# RePhone_core_2G-Atmel32u4_v1_0.net
KiCad netlist of a schematic drawn in EAGLE
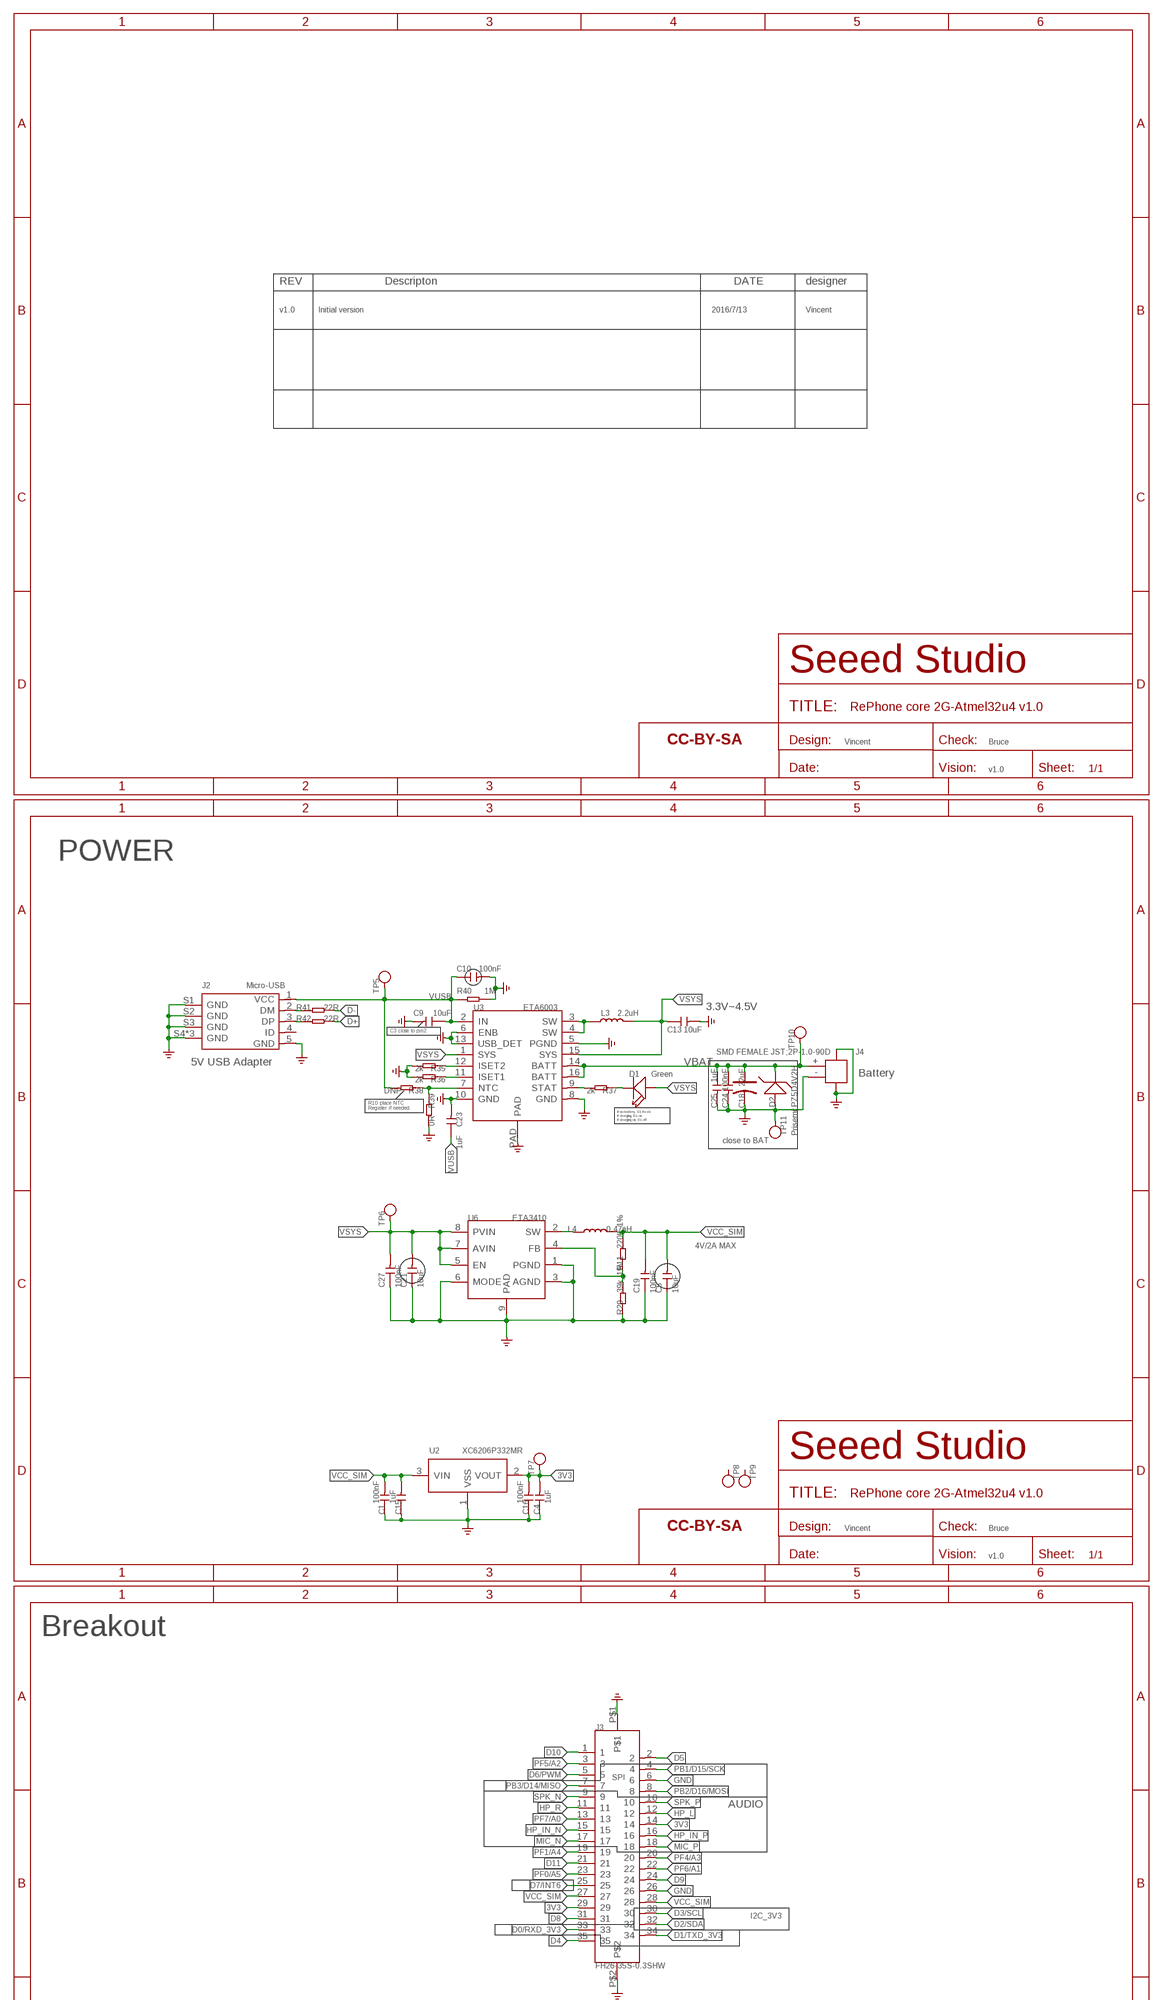
[diagram p0: schematic, sheet 1, part 1 of 2]
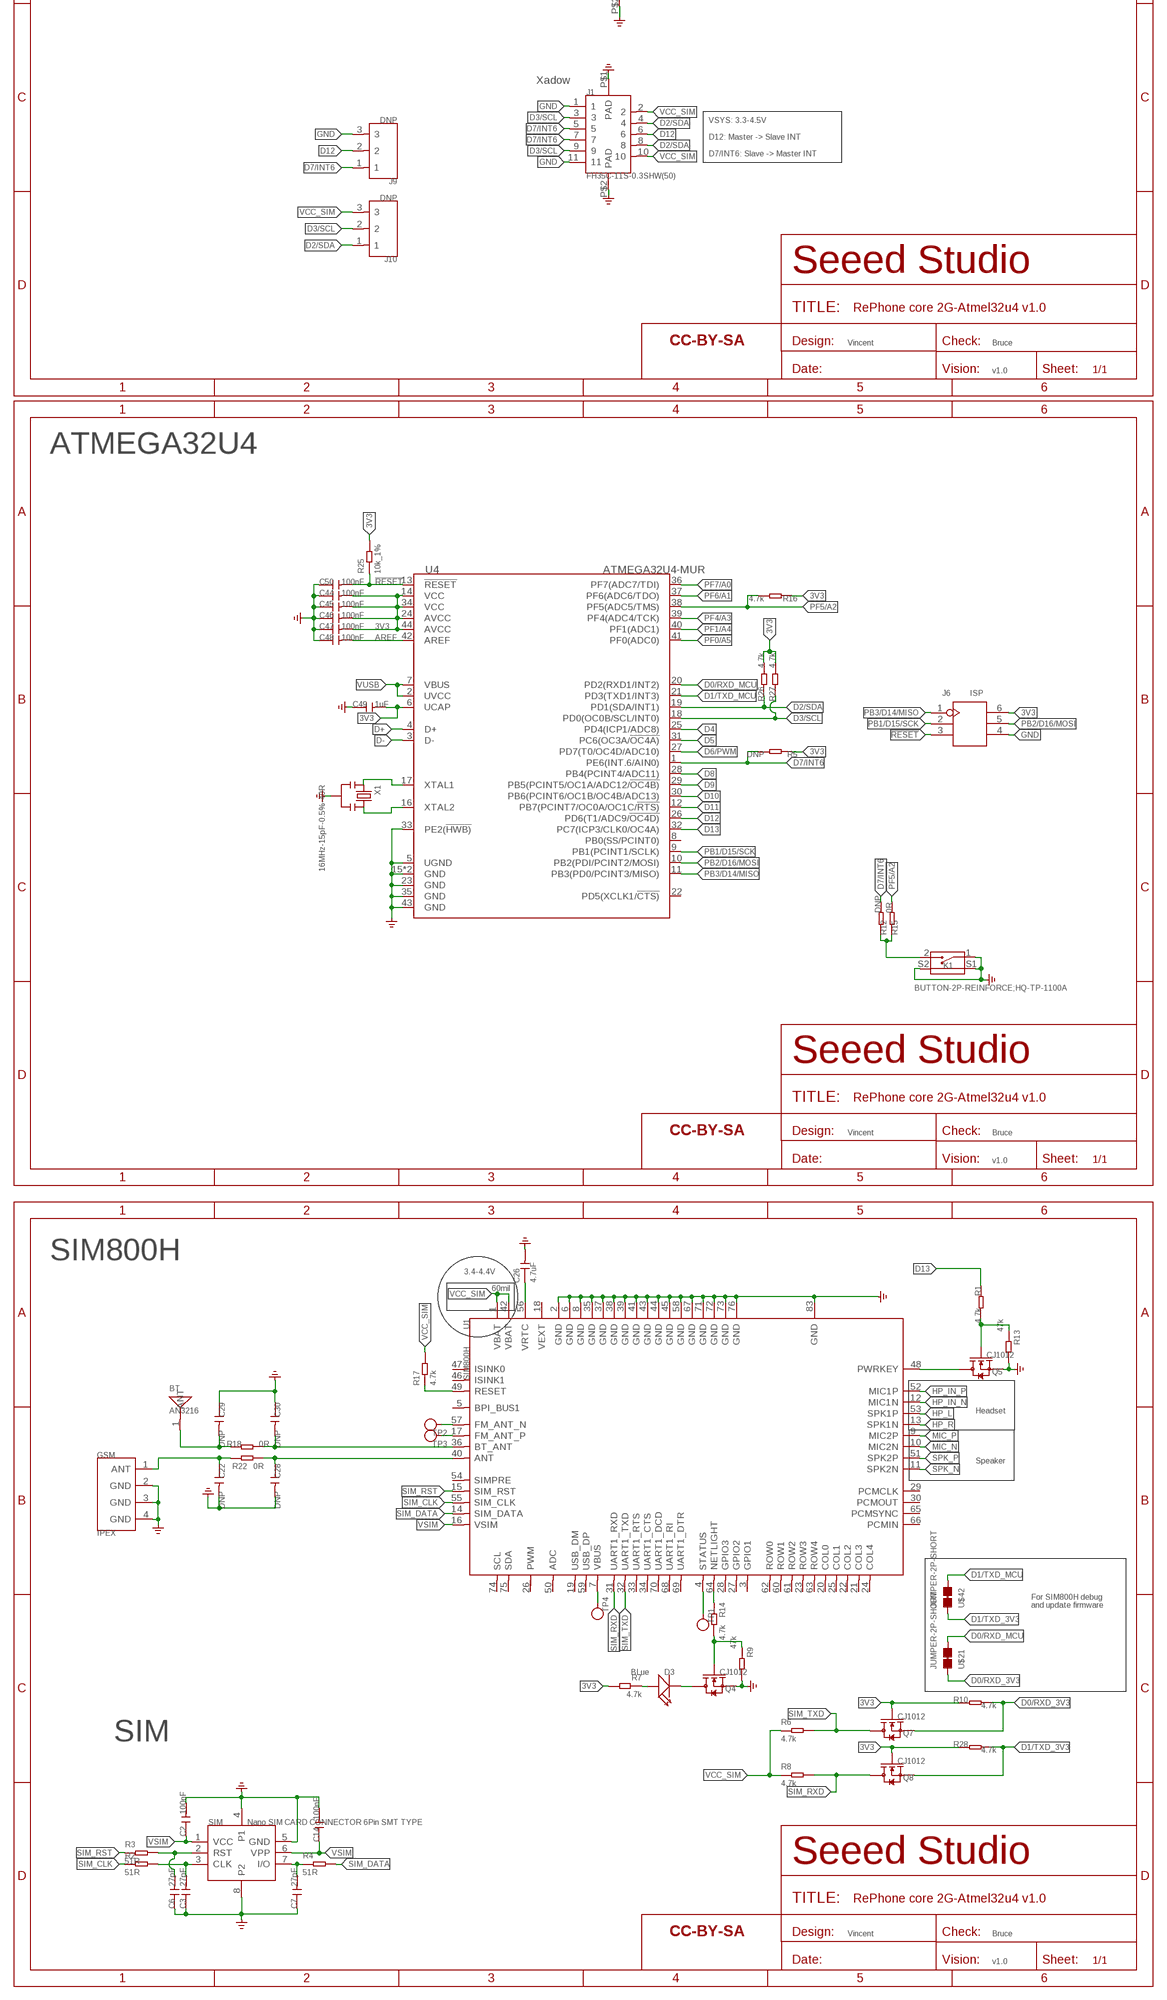
[diagram p1: schematic, sheet 1, part 2 of 2]

(export (version "E")
  (design (tool "Eeschema 10.0.6"))
  (components
    (comp (ref "BT")
      (value "AN3216")
      (footprint "eagle-import:ANT-SMD2P-3.2X1.6X1.04MM")
      (libsource (lib "eagle-import") (part "ANTENNA-AN3216"))
    )
    (comp (ref "C1")
      (value "100nF")
      (footprint "eagle-import:C0201")
      (libsource (lib "eagle-import") (part "CAP-0201"))
    )
    (comp (ref "C2")
      (value "100nF")
      (footprint "eagle-import:C0201")
      (libsource (lib "eagle-import") (part "CAP-0201"))
    )
    (comp (ref "C3")
      (value "27pF")
      (footprint "eagle-import:C0201")
      (libsource (lib "eagle-import") (part "CAP-0201"))
    )
    (comp (ref "C4")
      (value "1uF")
      (footprint "eagle-import:C0402")
      (libsource (lib "eagle-import") (part "CAP-0402"))
    )
    (comp (ref "C5")
      (value "10uF")
      (footprint "eagle-import:C0603")
      (libsource (lib "eagle-import") (part "CAP-0603"))
    )
    (comp (ref "C6")
      (value "27pF")
      (footprint "eagle-import:C0201")
      (libsource (lib "eagle-import") (part "CAP-0201"))
    )
    (comp (ref "C7")
      (value "27pF")
      (footprint "eagle-import:C0201")
      (libsource (lib "eagle-import") (part "CAP-0201"))
    )
    (comp (ref "C9")
      (value "10uF")
      (footprint "eagle-import:C0603")
      (libsource (lib "eagle-import") (part "CAP-0603"))
    )
    (comp (ref "C10")
      (value "100nF")
      (footprint "eagle-import:C0201")
      (libsource (lib "eagle-import") (part "CAP-0201"))
    )
    (comp (ref "C13")
      (value "10uF")
      (footprint "eagle-import:C0603")
      (libsource (lib "eagle-import") (part "CAP-0603"))
    )
    (comp (ref "C14")
      (value "100nF")
      (footprint "eagle-import:C0201")
      (libsource (lib "eagle-import") (part "CAP-0201"))
    )
    (comp (ref "C15")
      (value "1uF")
      (footprint "eagle-import:C0402")
      (libsource (lib "eagle-import") (part "CAP-0402"))
    )
    (comp (ref "C16")
      (value "100nF")
      (footprint "eagle-import:C0201")
      (libsource (lib "eagle-import") (part "CAP-0201"))
    )
    (comp (ref "C18")
      (value "22uF")
      (footprint "eagle-import:AVX-A")
      (libsource (lib "eagle-import") (part "CAP-POLAR-AVX-A"))
    )
    (comp (ref "C19")
      (value "100nF")
      (footprint "eagle-import:C0201")
      (libsource (lib "eagle-import") (part "CAP-0201"))
    )
    (comp (ref "C21")
      (value "10uF")
      (footprint "eagle-import:C0603")
      (libsource (lib "eagle-import") (part "CAP-0603"))
    )
    (comp (ref "C22")
      (value "DNP")
      (footprint "eagle-import:C0201")
      (libsource (lib "eagle-import") (part "CAP-0201"))
    )
    (comp (ref "C23")
      (value "1uF")
      (footprint "eagle-import:C0402")
      (libsource (lib "eagle-import") (part "CAP-0402"))
    )
    (comp (ref "C24")
      (value "100nF")
      (footprint "eagle-import:C0201")
      (libsource (lib "eagle-import") (part "CAP-0201"))
    )
    (comp (ref "C25")
      (value "1uF")
      (footprint "eagle-import:C0402")
      (libsource (lib "eagle-import") (part "CAP-0402"))
    )
    (comp (ref "C26")
      (value "4.7uF")
      (footprint "eagle-import:C0603")
      (libsource (lib "eagle-import") (part "CAP-0603"))
    )
    (comp (ref "C27")
      (value "100nF")
      (footprint "eagle-import:C0201")
      (libsource (lib "eagle-import") (part "CAP-0201"))
    )
    (comp (ref "C28")
      (value "DNP")
      (footprint "eagle-import:C0201")
      (libsource (lib "eagle-import") (part "CAP-0201"))
    )
    (comp (ref "C29")
      (value "DNP")
      (footprint "eagle-import:C0201")
      (libsource (lib "eagle-import") (part "CAP-0201"))
    )
    (comp (ref "C30")
      (value "DNP")
      (footprint "eagle-import:C0201")
      (libsource (lib "eagle-import") (part "CAP-0201"))
    )
    (comp (ref "C44")
      (value "100nF")
      (footprint "eagle-import:C0201")
      (libsource (lib "eagle-import") (part "CAP-0201"))
    )
    (comp (ref "C45")
      (value "100nF")
      (footprint "eagle-import:C0201")
      (libsource (lib "eagle-import") (part "CAP-0201"))
    )
    (comp (ref "C46")
      (value "100nF")
      (footprint "eagle-import:C0201")
      (libsource (lib "eagle-import") (part "CAP-0201"))
    )
    (comp (ref "C47")
      (value "100nF")
      (footprint "eagle-import:C0201")
      (libsource (lib "eagle-import") (part "CAP-0201"))
    )
    (comp (ref "C48")
      (value "100nF")
      (footprint "eagle-import:C0201")
      (libsource (lib "eagle-import") (part "CAP-0201"))
    )
    (comp (ref "C49")
      (value "1uF")
      (footprint "eagle-import:C0402")
      (libsource (lib "eagle-import") (part "CAP-0402"))
    )
    (comp (ref "C50")
      (value "100nF")
      (footprint "eagle-import:C0201")
      (libsource (lib "eagle-import") (part "CAP-0201"))
    )
    (comp (ref "D1")
      (value "Green")
      (footprint "eagle-import:LED-0402")
      (libsource (lib "eagle-import") (part "LED-0402"))
    )
    (comp (ref "D2")
      (value "Prisemi;PZ5D4V2H")
      (footprint "eagle-import:SOD-523")
      (libsource (lib "eagle-import") (part "D-ZENER-2P'BZX584CX'"))
    )
    (comp (ref "D3")
      (value "BLue")
      (footprint "eagle-import:LED-0402")
      (libsource (lib "eagle-import") (part "LED-0402"))
    )
    (comp (ref "FR1")
      (value "SEEEDSTUDIO-OPEN-SCH-FRAME")
      (footprint "eagle-import:SEEEDSTUDIO-PCB-FRAME")
      (libsource (lib "eagle-import") (part "SEEEDSTUDIO-OPEN-SCH-FRAME"))
    )
    (comp (ref "FR2")
      (value "SEEEDSTUDIO-OPEN-SCH-FRAME")
      (footprint "eagle-import:SEEEDSTUDIO-PCB-FRAME")
      (libsource (lib "eagle-import") (part "SEEEDSTUDIO-OPEN-SCH-FRAME"))
    )
    (comp (ref "GSM")
      (value "IPEX")
      (footprint "eagle-import:ANT-IPEX4-1.7X1.7MM")
      (libsource (lib "eagle-import") (part "ANT_IPEX"))
    )
    (comp (ref "J1")
      (value "FH35C-11S-0.3SHW(50)")
      (footprint "eagle-import:FPC11-SMD-0.3(FH35C)")
      (libsource (lib "eagle-import") (part "FPC-CONNECTER-11P(FH35C-11S-0.3SHW(50))"))
    )
    (comp (ref "J2")
      (value "Micro-USB")
      (footprint "eagle-import:MICRO-USB5+4P-SMD-0.65-B")
      (libsource (lib "eagle-import") (part "MICRO-USB5+4P5+4P"))
    )
    (comp (ref "J3")
      (value "FH26-35S-0.3SHW")
      (footprint "eagle-import:FPC35-SMD-0.3(FH26W)")
      (libsource (lib "eagle-import") (part "FPC-CONNECTER-35P(FH26W-35S-0.3SHW(10))"))
    )
    (comp (ref "J4")
      (value "SMD FEMALE JST;2P-1.0-90D")
      (footprint "eagle-import:HW2-SMD-1.0-90D")
      (libsource (lib "eagle-import") (part "JST-2P-SMD'1.0'"))
    )
    (comp (ref "J6")
      (value "ISP")
      (footprint "eagle-import:H2X3-SMD-2.0(1.143)")
      (libsource (lib "eagle-import") (part "HEADER-2X3P-2.0-1.143"))
    )
    (comp (ref "J9")
      (value "DNP")
      (footprint "eagle-import:3P-DIP-2")
      (libsource (lib "eagle-import") (part "HEADER3"))
    )
    (comp (ref "J10")
      (value "DNP")
      (footprint "eagle-import:3P-DIP-2")
      (libsource (lib "eagle-import") (part "HEADER3"))
    )
    (comp (ref "K1")
      (value "BUTTON-2P-REINFORCE;HQ-TP-1100A")
      (footprint "eagle-import:SW4-SMD-4.5X3.8X1.8MM-90D")
      (libsource (lib "eagle-import") (part "BUTTON-2+2P'HQ-TP-1100A'"))
    )
    (comp (ref "L3")
      (value "2.2uH")
      (footprint "eagle-import:L0805")
      (libsource (lib "eagle-import") (part "INDUCTOR/FERRITE-BEAD'0805'"))
    )
    (comp (ref "L4")
      (value "0.47uH")
      (footprint "eagle-import:L201610")
      (libsource (lib "eagle-import") (part "L-MPM201610SR33_T"))
    )
    (comp (ref "Q4")
      (value "CJ1012")
      (footprint "eagle-import:SOT-523")
      (libsource (lib "eagle-import") (part "MOSFET-N"))
    )
    (comp (ref "Q5")
      (value "CJ1012")
      (footprint "eagle-import:SOT-523")
      (libsource (lib "eagle-import") (part "MOSFET-N"))
    )
    (comp (ref "Q7")
      (value "CJ1012")
      (footprint "eagle-import:SOT-523")
      (libsource (lib "eagle-import") (part "MOSFET-N"))
    )
    (comp (ref "Q8")
      (value "CJ1012")
      (footprint "eagle-import:SOT-523")
      (libsource (lib "eagle-import") (part "MOSFET-N"))
    )
    (comp (ref "R1")
      (value "4.7k")
      (footprint "eagle-import:R0201")
      (libsource (lib "eagle-import") (part "RES-0201"))
    )
    (comp (ref "R2")
      (value "51R")
      (footprint "eagle-import:R0201")
      (libsource (lib "eagle-import") (part "RES-0201"))
    )
    (comp (ref "R3")
      (value "51R")
      (footprint "eagle-import:R0201")
      (libsource (lib "eagle-import") (part "RES-0201"))
    )
    (comp (ref "R4")
      (value "51R")
      (footprint "eagle-import:R0201")
      (libsource (lib "eagle-import") (part "RES-0201"))
    )
    (comp (ref "R5")
      (value "DNP")
      (footprint "eagle-import:R0201")
      (libsource (lib "eagle-import") (part "RES-0201"))
    )
    (comp (ref "R6")
      (value "4.7k")
      (footprint "eagle-import:R0201")
      (libsource (lib "eagle-import") (part "RES-0201"))
    )
    (comp (ref "R7")
      (value "4.7k")
      (footprint "eagle-import:R0201")
      (libsource (lib "eagle-import") (part "RES-0201"))
    )
    (comp (ref "R8")
      (value "4.7k")
      (footprint "eagle-import:R0201")
      (libsource (lib "eagle-import") (part "RES-0201"))
    )
    (comp (ref "R9")
      (value "47k")
      (footprint "eagle-import:R0201")
      (libsource (lib "eagle-import") (part "RES-0201"))
    )
    (comp (ref "R10")
      (value "4.7k")
      (footprint "eagle-import:R0201")
      (libsource (lib "eagle-import") (part "RES-0201"))
    )
    (comp (ref "R11")
      (value "220k_1%")
      (footprint "eagle-import:R0201")
      (libsource (lib "eagle-import") (part "RES-0201"))
    )
    (comp (ref "R12")
      (value "DNP")
      (footprint "eagle-import:R0201")
      (libsource (lib "eagle-import") (part "RES-0201"))
    )
    (comp (ref "R13")
      (value "47k")
      (footprint "eagle-import:R0201")
      (libsource (lib "eagle-import") (part "RES-0201"))
    )
    (comp (ref "R14")
      (value "4.7k")
      (footprint "eagle-import:R0201")
      (libsource (lib "eagle-import") (part "RES-0201"))
    )
    (comp (ref "R15")
      (value "0R")
      (footprint "eagle-import:R0201")
      (libsource (lib "eagle-import") (part "RES-0201"))
    )
    (comp (ref "R16")
      (value "4.7k")
      (footprint "eagle-import:R0201")
      (libsource (lib "eagle-import") (part "RES-0201"))
    )
    (comp (ref "R17")
      (value "4.7k")
      (footprint "eagle-import:R0201")
      (libsource (lib "eagle-import") (part "RES-0201"))
    )
    (comp (ref "R18")
      (value "0R")
      (footprint "eagle-import:R0201")
      (libsource (lib "eagle-import") (part "RES-0201"))
    )
    (comp (ref "R22")
      (value "0R")
      (footprint "eagle-import:R0201")
      (libsource (lib "eagle-import") (part "RES-0201"))
    )
    (comp (ref "R25")
      (value "10k_1%")
      (footprint "eagle-import:R0201")
      (libsource (lib "eagle-import") (part "RES-0201"))
    )
    (comp (ref "R26")
      (value "4.7k")
      (footprint "eagle-import:R0201")
      (libsource (lib "eagle-import") (part "RES-0201"))
    )
    (comp (ref "R27")
      (value "4.7k")
      (footprint "eagle-import:R0201")
      (libsource (lib "eagle-import") (part "RES-0201"))
    )
    (comp (ref "R28")
      (value "4.7k")
      (footprint "eagle-import:R0201")
      (libsource (lib "eagle-import") (part "RES-0201"))
    )
    (comp (ref "R29")
      (value "39k_1%")
      (footprint "eagle-import:R0201")
      (libsource (lib "eagle-import") (part "RES-0201"))
    )
    (comp (ref "R35")
      (value "2k")
      (footprint "eagle-import:R0201")
      (libsource (lib "eagle-import") (part "RES-0201"))
    )
    (comp (ref "R36")
      (value "2k")
      (footprint "eagle-import:R0201")
      (libsource (lib "eagle-import") (part "RES-0201"))
    )
    (comp (ref "R37")
      (value "2k")
      (footprint "eagle-import:R0201")
      (libsource (lib "eagle-import") (part "RES-0201"))
    )
    (comp (ref "R38")
      (value "DNP")
      (footprint "eagle-import:R0201")
      (libsource (lib "eagle-import") (part "RES-0201"))
    )
    (comp (ref "R39")
      (value "0R")
      (footprint "eagle-import:R0201")
      (libsource (lib "eagle-import") (part "RES-0201"))
    )
    (comp (ref "R40")
      (value "1M")
      (footprint "eagle-import:R0201")
      (libsource (lib "eagle-import") (part "RES-0201"))
    )
    (comp (ref "R41")
      (value "22R")
      (footprint "eagle-import:R0201")
      (libsource (lib "eagle-import") (part "RES-0201"))
    )
    (comp (ref "R42")
      (value "22R")
      (footprint "eagle-import:R0201")
      (libsource (lib "eagle-import") (part "RES-0201"))
    )
    (comp (ref "SIM")
      (value "Nano SIM CARD CONNECTOR 6Pin SMT TYPE")
      (footprint "eagle-import:NANO-SIM6+2P-SMD-12.3X10X1.5MM")
      (libsource (lib "eagle-import") (part "NANO-SIM-6+2P-SMD"))
    )
    (comp (ref "TP1")
      (value "TEST-POINT-23")
      (footprint "eagle-import:TP-D23MIL")
      (libsource (lib "eagle-import") (part "TEST-POINT-23"))
    )
    (comp (ref "TP2")
      (value "TEST-POINT'4545'")
      (footprint "eagle-import:TP-D45MIL")
      (fields (field (name "PARTNO") "DNP"))
      (libsource (lib "eagle-import") (part "TEST-POINT'4545'"))
    )
    (comp (ref "TP3")
      (value "TEST-POINT'4545'")
      (footprint "eagle-import:TP-D45MIL")
      (fields (field (name "PARTNO") "DNP"))
      (libsource (lib "eagle-import") (part "TEST-POINT'4545'"))
    )
    (comp (ref "TP4")
      (value "TEST-POINT-23")
      (footprint "eagle-import:TP-D23MIL")
      (libsource (lib "eagle-import") (part "TEST-POINT-23"))
    )
    (comp (ref "TP5")
      (value "TEST-POINT-23")
      (footprint "eagle-import:TP-D23MIL")
      (libsource (lib "eagle-import") (part "TEST-POINT-23"))
    )
    (comp (ref "TP6")
      (value "TEST-POINT-23")
      (footprint "eagle-import:TP-D23MIL")
      (libsource (lib "eagle-import") (part "TEST-POINT-23"))
    )
    (comp (ref "TP7")
      (value "TEST-POINT-23")
      (footprint "eagle-import:TP-D23MIL")
      (libsource (lib "eagle-import") (part "TEST-POINT-23"))
    )
    (comp (ref "TP8")
      (value "TEST-POINT-23")
      (footprint "eagle-import:TP-D23MIL")
      (libsource (lib "eagle-import") (part "TEST-POINT-23"))
    )
    (comp (ref "TP9")
      (value "TEST-POINT-23")
      (footprint "eagle-import:TP-D23MIL")
      (libsource (lib "eagle-import") (part "TEST-POINT-23"))
    )
    (comp (ref "TP10")
      (value "TEST-POINT-23")
      (footprint "eagle-import:TP-D23MIL")
      (libsource (lib "eagle-import") (part "TEST-POINT-23"))
    )
    (comp (ref "TP11")
      (value "TEST-POINT-23")
      (footprint "eagle-import:TP-D23MIL")
      (libsource (lib "eagle-import") (part "TEST-POINT-23"))
    )
    (comp (ref "U$1")
      (value "SEEEDSTUDIO-OPEN-SCH-FRAME")
      (footprint "eagle-import:SEEEDSTUDIO-PCB-FRAME")
      (libsource (lib "eagle-import") (part "SEEEDSTUDIO-OPEN-SCH-FRAME"))
    )
    (comp (ref "U$3")
      (value "SEEEDSTUDIO-OPEN-SCH-FRAME")
      (footprint "eagle-import:SEEEDSTUDIO-PCB-FRAME")
      (libsource (lib "eagle-import") (part "SEEEDSTUDIO-OPEN-SCH-FRAME"))
    )
    (comp (ref "U$5")
      (value "SEEEDSTUDIO-OPEN-SCH-FRAME")
      (footprint "eagle-import:SEEEDSTUDIO-PCB-FRAME")
      (libsource (lib "eagle-import") (part "SEEEDSTUDIO-OPEN-SCH-FRAME"))
    )
    (comp (ref "U$21")
      (value "JUMPER-2P-SHORT")
      (footprint "eagle-import:2P-SMD-SHORT")
      (libsource (lib "eagle-import") (part "JUMPER-2P-SHORT"))
    )
    (comp (ref "U$42")
      (value "JUMPER-2P-SHORT")
      (footprint "eagle-import:2P-SMD-SHORT")
      (libsource (lib "eagle-import") (part "JUMPER-2P-SHORT"))
    )
    (comp (ref "U1")
      (value "SIM800H")
      (footprint "eagle-import:GPRS88-SMD-1.4-17.8X45.8X2.4MM")
      (libsource (lib "eagle-import") (part "MOUDLE-GPRS-SIM800H"))
    )
    (comp (ref "U2")
      (value "XC6206P332MR")
      (footprint "eagle-import:SOT-23")
      (libsource (lib "eagle-import") (part "PMIC-XC6206PMR"))
    )
    (comp (ref "U3")
      (value "ETA6003")
      (footprint "eagle-import:QFN16GA-0.5-3X3MM")
      (libsource (lib "eagle-import") (part "PMIC-ETA6003"))
    )
    (comp (ref "U4")
      (value "ATMEGA32U4-MUR")
      (footprint "eagle-import:QFN44G-0.5-7X7MM")
      (libsource (lib "eagle-import") (part "MCU-ATMEGA32U4-MUR"))
    )
    (comp (ref "U6")
      (value "ETA3410")
      (footprint "eagle-import:DFN8G-0.5-2X2MM")
      (libsource (lib "eagle-import") (part "CONVERTER-ETA3410"))
    )
    (comp (ref "X1")
      (value "16MHz-15pF-0.5%-40R")
      (footprint "eagle-import:RESONATOR3-SMD-3.6X1.3X0.8MM")
      (libsource (lib "eagle-import") (part "CRYSTAL-RESONATOR'SMD'"))
    )
  )
  (nets
    (net (code "1") (name "/AREF") (class "Default")
      (node (ref "C48") (pin "2") (pinfunction "2_2") (pintype "passive"))
      (node (ref "U4") (pin "42") (pinfunction "AREF_42") (pintype "bidirectional"))
    )
    (net (code "2") (name "/VBAT") (class "Default")
      (node (ref "C18") (pin "+") (pinfunction "+_+") (pintype "passive"))
      (node (ref "C24") (pin "1") (pinfunction "1_1") (pintype "passive"))
      (node (ref "C25") (pin "1") (pinfunction "1_1") (pintype "passive"))
      (node (ref "D2") (pin "-") (pinfunction "-_-") (pintype "bidirectional"))
      (node (ref "J4") (pin "+") (pinfunction "1_+") (pintype "bidirectional"))
      (node (ref "TP10") (pin "T") (pinfunction "T_T") (pintype "bidirectional"))
      (node (ref "U3") (pin "14") (pinfunction "BATT_14") (pintype "bidirectional"))
      (node (ref "U3") (pin "16") (pinfunction "BATT_16") (pintype "bidirectional"))
    )
    (net (code "3") (name "/~{RESET}") (class "Default")
      (node (ref "C50") (pin "2") (pinfunction "2_2") (pintype "passive"))
      (node (ref "J6") (pin "3") (pinfunction "3_3") (pintype "bidirectional"))
      (node (ref "R25") (pin "1") (pinfunction "1_1") (pintype "passive"))
      (node (ref "U4") (pin "13") (pinfunction "~{RESET}_13") (pintype "bidirectional"))
    )
    (net (code "4") (name "3V3") (class "Default")
      (node (ref "C16") (pin "2") (pinfunction "2_2") (pintype "passive"))
      (node (ref "C4") (pin "2") (pinfunction "2_2") (pintype "passive"))
      (node (ref "C44") (pin "2") (pinfunction "2_2") (pintype "passive"))
      (node (ref "C45") (pin "2") (pinfunction "2_2") (pintype "passive"))
      (node (ref "C46") (pin "2") (pinfunction "2_2") (pintype "passive"))
      (node (ref "C47") (pin "2") (pinfunction "2_2") (pintype "passive"))
      (node (ref "C49") (pin "2") (pinfunction "2_2") (pintype "passive"))
      (node (ref "J3") (pin "14") (pinfunction "14_14") (pintype "bidirectional"))
      (node (ref "J3") (pin "29") (pinfunction "29_29") (pintype "bidirectional"))
      (node (ref "J6") (pin "6") (pinfunction "6_6") (pintype "bidirectional"))
      (node (ref "Q7") (pin "1") (pinfunction "G_1") (pintype "passive"))
      (node (ref "Q8") (pin "1") (pinfunction "G_1") (pintype "passive"))
      (node (ref "R10") (pin "1") (pinfunction "1_1") (pintype "passive"))
      (node (ref "R16") (pin "1") (pinfunction "1_1") (pintype "passive"))
      (node (ref "R25") (pin "2") (pinfunction "2_2") (pintype "passive"))
      (node (ref "R26") (pin "2") (pinfunction "2_2") (pintype "passive"))
      (node (ref "R27") (pin "2") (pinfunction "2_2") (pintype "passive"))
      (node (ref "R28") (pin "1") (pinfunction "1_1") (pintype "passive"))
      (node (ref "R5") (pin "1") (pinfunction "1_1") (pintype "passive"))
      (node (ref "R7") (pin "2") (pinfunction "2_2") (pintype "passive"))
      (node (ref "TP7") (pin "T") (pinfunction "T_T") (pintype "bidirectional"))
      (node (ref "U2") (pin "2") (pinfunction "VOUT_2") (pintype "bidirectional"))
      (node (ref "U4") (pin "14") (pinfunction "VCC_14") (pintype "bidirectional"))
      (node (ref "U4") (pin "24") (pinfunction "AVCC_24") (pintype "bidirectional"))
      (node (ref "U4") (pin "34") (pinfunction "VCC_34") (pintype "bidirectional"))
      (node (ref "U4") (pin "44") (pinfunction "AVCC_44") (pintype "bidirectional"))
      (node (ref "U4") (pin "6") (pinfunction "UCAP_6") (pintype "bidirectional"))
    )
    (net (code "5") (name "D+") (class "Default")
      (node (ref "R42") (pin "2") (pinfunction "2_2") (pintype "passive"))
      (node (ref "U4") (pin "4") (pinfunction "D+_4") (pintype "bidirectional"))
    )
    (net (code "6") (name "D-") (class "Default")
      (node (ref "R41") (pin "2") (pinfunction "2_2") (pintype "passive"))
      (node (ref "U4") (pin "3") (pinfunction "D-_3") (pintype "bidirectional"))
    )
    (net (code "7") (name "D0{slash}RXD_3V3") (class "Default")
      (node (ref "J3") (pin "33") (pinfunction "33_33") (pintype "bidirectional"))
      (node (ref "Q7") (pin "2") (pinfunction "S_2") (pintype "passive"))
      (node (ref "R10") (pin "2") (pinfunction "2_2") (pintype "passive"))
      (node (ref "U$21") (pin "1") (pinfunction "1_1") (pintype "bidirectional"))
    )
    (net (code "8") (name "D0{slash}RXD_MCU") (class "Default")
      (node (ref "U$21") (pin "2") (pinfunction "2_2") (pintype "bidirectional"))
      (node (ref "U4") (pin "20") (pinfunction "PD2(RXD1/INT2)_20") (pintype "bidirectional"))
    )
    (net (code "9") (name "D1{slash}TXD_3V3") (class "Default")
      (node (ref "J3") (pin "34") (pinfunction "34_34") (pintype "bidirectional"))
      (node (ref "Q8") (pin "2") (pinfunction "S_2") (pintype "passive"))
      (node (ref "R28") (pin "2") (pinfunction "2_2") (pintype "passive"))
      (node (ref "U$42") (pin "1") (pinfunction "1_1") (pintype "bidirectional"))
    )
    (net (code "10") (name "D1{slash}TXD_MCU") (class "Default")
      (node (ref "U$42") (pin "2") (pinfunction "2_2") (pintype "bidirectional"))
      (node (ref "U4") (pin "21") (pinfunction "PD3(TXD1/INT3)_21") (pintype "bidirectional"))
    )
    (net (code "11") (name "D2{slash}SDA") (class "Default")
      (node (ref "J1") (pin "4") (pinfunction "4_4") (pintype "bidirectional"))
      (node (ref "J1") (pin "8") (pinfunction "8_8") (pintype "bidirectional"))
      (node (ref "J10") (pin "1") (pinfunction "1_1") (pintype "bidirectional"))
      (node (ref "J3") (pin "32") (pinfunction "32_32") (pintype "bidirectional"))
      (node (ref "R26") (pin "1") (pinfunction "1_1") (pintype "passive"))
      (node (ref "U4") (pin "19") (pinfunction "PD1(SDA/INT1)_19") (pintype "bidirectional"))
    )
    (net (code "12") (name "D3{slash}SCL") (class "Default")
      (node (ref "J1") (pin "3") (pinfunction "3_3") (pintype "bidirectional"))
      (node (ref "J1") (pin "9") (pinfunction "9_9") (pintype "bidirectional"))
      (node (ref "J10") (pin "2") (pinfunction "2_2") (pintype "bidirectional"))
      (node (ref "J3") (pin "30") (pinfunction "30_30") (pintype "bidirectional"))
      (node (ref "R27") (pin "1") (pinfunction "1_1") (pintype "passive"))
      (node (ref "U4") (pin "18") (pinfunction "PD0(OC0B/SCL/INT0)_18") (pintype "bidirectional"))
    )
    (net (code "13") (name "D4") (class "Default")
      (node (ref "J3") (pin "35") (pinfunction "35_35") (pintype "bidirectional"))
      (node (ref "U4") (pin "25") (pinfunction "PD4(ICP1/ADC8)_25") (pintype "bidirectional"))
    )
    (net (code "14") (name "D5") (class "Default")
      (node (ref "J3") (pin "2") (pinfunction "2_2") (pintype "bidirectional"))
      (node (ref "U4") (pin "31") (pinfunction "PC6(OC3A/~{OC4A})_31") (pintype "bidirectional"))
    )
    (net (code "15") (name "D6{slash}PWM") (class "Default")
      (node (ref "J3") (pin "5") (pinfunction "5_5") (pintype "bidirectional"))
      (node (ref "U4") (pin "27") (pinfunction "PD7(T0/OC4D/ADC10)_27") (pintype "bidirectional"))
    )
    (net (code "16") (name "D7{slash}INT6") (class "Default")
      (node (ref "J1") (pin "5") (pinfunction "5_5") (pintype "bidirectional"))
      (node (ref "J1") (pin "7") (pinfunction "7_7") (pintype "bidirectional"))
      (node (ref "J3") (pin "25") (pinfunction "25_25") (pintype "bidirectional"))
      (node (ref "J9") (pin "1") (pinfunction "1_1") (pintype "bidirectional"))
      (node (ref "R12") (pin "2") (pinfunction "2_2") (pintype "passive"))
      (node (ref "R5") (pin "2") (pinfunction "2_2") (pintype "passive"))
      (node (ref "U4") (pin "1") (pinfunction "PE6(INT.6/AIN0)_1") (pintype "bidirectional"))
    )
    (net (code "17") (name "D8") (class "Default")
      (node (ref "J3") (pin "31") (pinfunction "31_31") (pintype "bidirectional"))
      (node (ref "U4") (pin "28") (pinfunction "PB4(PCINT4/ADC11)_28") (pintype "bidirectional"))
    )
    (net (code "18") (name "D9") (class "Default")
      (node (ref "J3") (pin "24") (pinfunction "24_24") (pintype "bidirectional"))
      (node (ref "U4") (pin "29") (pinfunction "PB5(PCINT5/OC1A/ADC12/~{OC4B})_29") (pintype "bidirectional"))
    )
    (net (code "19") (name "D10") (class "Default")
      (node (ref "J3") (pin "1") (pinfunction "1_1") (pintype "bidirectional"))
      (node (ref "U4") (pin "30") (pinfunction "PB6(PCINT6/OC1B/OC4B/ADC13)_30") (pintype "bidirectional"))
    )
    (net (code "20") (name "D11") (class "Default")
      (node (ref "J3") (pin "21") (pinfunction "21_21") (pintype "bidirectional"))
      (node (ref "U4") (pin "12") (pinfunction "PB7(PCINT7/OC0A/OC1C/~{RTS})_12") (pintype "bidirectional"))
    )
    (net (code "21") (name "D12") (class "Default")
      (node (ref "J1") (pin "6") (pinfunction "6_6") (pintype "bidirectional"))
      (node (ref "J9") (pin "2") (pinfunction "2_2") (pintype "bidirectional"))
      (node (ref "U4") (pin "26") (pinfunction "PD6(T1/ADC9/~{OC4D})_26") (pintype "bidirectional"))
    )
    (net (code "22") (name "D13") (class "Default")
      (node (ref "R1") (pin "1") (pinfunction "1_1") (pintype "passive"))
      (node (ref "U4") (pin "32") (pinfunction "PC7(ICP3/CLK0/OC4A)_32") (pintype "bidirectional"))
    )
    (net (code "23") (name "GND") (class "Default")
      (node (ref "C1") (pin "1") (pinfunction "1_1") (pintype "passive"))
      (node (ref "C10") (pin "2") (pinfunction "2_2") (pintype "passive"))
      (node (ref "C13") (pin "2") (pinfunction "2_2") (pintype "passive"))
      (node (ref "C14") (pin "2") (pinfunction "2_2") (pintype "passive"))
      (node (ref "C15") (pin "1") (pinfunction "1_1") (pintype "passive"))
      (node (ref "C16") (pin "1") (pinfunction "1_1") (pintype "passive"))
      (node (ref "C18") (pin "-") (pinfunction "-_-") (pintype "passive"))
      (node (ref "C19") (pin "1") (pinfunction "1_1") (pintype "passive"))
      (node (ref "C2") (pin "2") (pinfunction "2_2") (pintype "passive"))
      (node (ref "C21") (pin "1") (pinfunction "1_1") (pintype "passive"))
      (node (ref "C22") (pin "2") (pinfunction "2_2") (pintype "passive"))
      (node (ref "C23") (pin "2") (pinfunction "2_2") (pintype "passive"))
      (node (ref "C24") (pin "2") (pinfunction "2_2") (pintype "passive"))
      (node (ref "C25") (pin "2") (pinfunction "2_2") (pintype "passive"))
      (node (ref "C26") (pin "2") (pinfunction "2_2") (pintype "passive"))
      (node (ref "C27") (pin "1") (pinfunction "1_1") (pintype "passive"))
      (node (ref "C28") (pin "2") (pinfunction "2_2") (pintype "passive"))
      (node (ref "C29") (pin "1") (pinfunction "1_1") (pintype "passive"))
      (node (ref "C3") (pin "1") (pinfunction "1_1") (pintype "passive"))
      (node (ref "C30") (pin "1") (pinfunction "1_1") (pintype "passive"))
      (node (ref "C4") (pin "1") (pinfunction "1_1") (pintype "passive"))
      (node (ref "C44") (pin "1") (pinfunction "1_1") (pintype "passive"))
      (node (ref "C45") (pin "1") (pinfunction "1_1") (pintype "passive"))
      (node (ref "C46") (pin "1") (pinfunction "1_1") (pintype "passive"))
      (node (ref "C47") (pin "1") (pinfunction "1_1") (pintype "passive"))
      (node (ref "C48") (pin "1") (pinfunction "1_1") (pintype "passive"))
      (node (ref "C49") (pin "1") (pinfunction "1_1") (pintype "passive"))
      (node (ref "C5") (pin "1") (pinfunction "1_1") (pintype "passive"))
      (node (ref "C50") (pin "1") (pinfunction "1_1") (pintype "passive"))
      (node (ref "C6") (pin "1") (pinfunction "1_1") (pintype "passive"))
      (node (ref "C7") (pin "1") (pinfunction "1_1") (pintype "passive"))
      (node (ref "C9") (pin "2") (pinfunction "2_2") (pintype "passive"))
      (node (ref "D2") (pin "+") (pinfunction "+_+") (pintype "bidirectional"))
      (node (ref "GSM") (pin "2") (pinfunction "GND_2") (pintype "bidirectional"))
      (node (ref "GSM") (pin "3") (pinfunction "GND_3") (pintype "bidirectional"))
      (node (ref "GSM") (pin "4") (pinfunction "GND_4") (pintype "bidirectional"))
      (node (ref "J1") (pin "1") (pinfunction "1_1") (pintype "bidirectional"))
      (node (ref "J1") (pin "11") (pinfunction "11_11") (pintype "bidirectional"))
      (node (ref "J1") (pin "P$1") (pinfunction "PAD_P$1") (pintype "bidirectional"))
      (node (ref "J1") (pin "P$2") (pinfunction "PAD_P$2") (pintype "bidirectional"))
      (node (ref "J2") (pin "5") (pinfunction "GND_5") (pintype "bidirectional"))
      (node (ref "J2") (pin "S1") (pinfunction "GND_S1") (pintype "bidirectional"))
      (node (ref "J2") (pin "S2") (pinfunction "GND_S2") (pintype "bidirectional"))
      (node (ref "J2") (pin "S3") (pinfunction "GND_S3") (pintype "bidirectional"))
      (node (ref "J2") (pin "S4") (pinfunction "GND_S4") (pintype "bidirectional"))
      (node (ref "J2") (pin "S5") (pinfunction "GND_S5") (pintype "bidirectional"))
      (node (ref "J2") (pin "S6") (pinfunction "GND_S6") (pintype "bidirectional"))
      (node (ref "J3") (pin "26") (pinfunction "26_26") (pintype "bidirectional"))
      (node (ref "J3") (pin "6") (pinfunction "6_6") (pintype "bidirectional"))
      (node (ref "J3") (pin "P$1") (pinfunction "P$1_P$1") (pintype "bidirectional"))
      (node (ref "J3") (pin "P$2") (pinfunction "P$2_P$2") (pintype "bidirectional"))
      (node (ref "J4") (pin "-") (pinfunction "2_-") (pintype "bidirectional"))
      (node (ref "J4") (pin "3") (pinfunction "3_3") (pintype "bidirectional"))
      (node (ref "J4") (pin "4") (pinfunction "4_4") (pintype "bidirectional"))
      (node (ref "J6") (pin "4") (pinfunction "4_4") (pintype "bidirectional"))
      (node (ref "J9") (pin "3") (pinfunction "3_3") (pintype "bidirectional"))
      (node (ref "K1") (pin "1") (pinfunction "1_1") (pintype "bidirectional"))
      (node (ref "K1") (pin "S1") (pinfunction "S1_S1") (pintype "bidirectional"))
      (node (ref "K1") (pin "S2") (pinfunction "S2_S2") (pintype "bidirectional"))
      (node (ref "Q4") (pin "2") (pinfunction "S_2") (pintype "passive"))
      (node (ref "Q5") (pin "2") (pinfunction "S_2") (pintype "passive"))
      (node (ref "R13") (pin "2") (pinfunction "2_2") (pintype "passive"))
      (node (ref "R29") (pin "1") (pinfunction "1_1") (pintype "passive"))
      (node (ref "R35") (pin "2") (pinfunction "2_2") (pintype "passive"))
      (node (ref "R36") (pin "2") (pinfunction "2_2") (pintype "passive"))
      (node (ref "R39") (pin "2") (pinfunction "2_2") (pintype "passive"))
      (node (ref "R40") (pin "2") (pinfunction "2_2") (pintype "passive"))
      (node (ref "R9") (pin "2") (pinfunction "2_2") (pintype "passive"))
      (node (ref "SIM") (pin "4") (pinfunction "P1_4") (pintype "bidirectional"))
      (node (ref "SIM") (pin "5") (pinfunction "GND_5") (pintype "bidirectional"))
      (node (ref "SIM") (pin "8") (pinfunction "P2_8") (pintype "bidirectional"))
      (node (ref "TP11") (pin "T") (pinfunction "T_T") (pintype "bidirectional"))
      (node (ref "U1") (pin "2") (pinfunction "GND_2") (pintype "bidirectional"))
      (node (ref "U1") (pin "35") (pinfunction "GND_35") (pintype "bidirectional"))
      (node (ref "U1") (pin "37") (pinfunction "GND_37") (pintype "bidirectional"))
      (node (ref "U1") (pin "38") (pinfunction "GND_38") (pintype "bidirectional"))
      (node (ref "U1") (pin "39") (pinfunction "GND_39") (pintype "bidirectional"))
      (node (ref "U1") (pin "41") (pinfunction "GND_41") (pintype "bidirectional"))
      (node (ref "U1") (pin "43") (pinfunction "GND_43") (pintype "bidirectional"))
      (node (ref "U1") (pin "44") (pinfunction "GND_44") (pintype "bidirectional"))
      (node (ref "U1") (pin "45") (pinfunction "GND_45") (pintype "bidirectional"))
      (node (ref "U1") (pin "58") (pinfunction "GND_58") (pintype "bidirectional"))
      (node (ref "U1") (pin "6") (pinfunction "GND_6") (pintype "bidirectional"))
      (node (ref "U1") (pin "67") (pinfunction "GND_67") (pintype "bidirectional"))
      (node (ref "U1") (pin "71") (pinfunction "GND_71") (pintype "bidirectional"))
      (node (ref "U1") (pin "72") (pinfunction "GND_72") (pintype "bidirectional"))
      (node (ref "U1") (pin "73") (pinfunction "GND_73") (pintype "bidirectional"))
      (node (ref "U1") (pin "76") (pinfunction "GND_76") (pintype "bidirectional"))
      (node (ref "U1") (pin "8") (pinfunction "GND_8") (pintype "bidirectional"))
      (node (ref "U1") (pin "83") (pinfunction "GND_83") (pintype "bidirectional"))
      (node (ref "U2") (pin "1") (pinfunction "VSS_1") (pintype "bidirectional"))
      (node (ref "U3") (pin "10") (pinfunction "GND_10") (pintype "bidirectional"))
      (node (ref "U3") (pin "13") (pinfunction "USB_DET_13") (pintype "bidirectional"))
      (node (ref "U3") (pin "5") (pinfunction "PGND_5") (pintype "bidirectional"))
      (node (ref "U3") (pin "6") (pinfunction "ENB_6") (pintype "bidirectional"))
      (node (ref "U3") (pin "8") (pinfunction "GND_8") (pintype "bidirectional"))
      (node (ref "U3") (pin "PAD") (pinfunction "PAD_PAD") (pintype "bidirectional"))
      (node (ref "U4") (pin "15") (pinfunction "GND_15") (pintype "bidirectional"))
      (node (ref "U4") (pin "23") (pinfunction "GND_23") (pintype "bidirectional"))
      (node (ref "U4") (pin "33") (pinfunction "PE2(~{HWB})_33") (pintype "bidirectional"))
      (node (ref "U4") (pin "35") (pinfunction "GND_35") (pintype "bidirectional"))
      (node (ref "U4") (pin "43") (pinfunction "GND_43") (pintype "bidirectional"))
      (node (ref "U4") (pin "5") (pinfunction "UGND_5") (pintype "bidirectional"))
      (node (ref "U4") (pin "TAB") (pinfunction "GND_TAB") (pintype "bidirectional"))
      (node (ref "U6") (pin "1") (pinfunction "PGND_1") (pintype "bidirectional"))
      (node (ref "U6") (pin "3") (pinfunction "AGND_3") (pintype "bidirectional"))
      (node (ref "U6") (pin "6") (pinfunction "MODE_6") (pintype "bidirectional"))
      (node (ref "U6") (pin "9") (pinfunction "PAD_9") (pintype "bidirectional"))
      (node (ref "X1") (pin "2") (pinfunction "2_2") (pintype "passive"))
    )
    (net (code "24") (name "HP_IN_N") (class "Default")
      (node (ref "J3") (pin "15") (pinfunction "15_15") (pintype "bidirectional"))
      (node (ref "U1") (pin "12") (pinfunction "MIC1N_12") (pintype "bidirectional"))
    )
    (net (code "25") (name "HP_IN_P") (class "Default")
      (node (ref "J3") (pin "16") (pinfunction "16_16") (pintype "bidirectional"))
      (node (ref "U1") (pin "52") (pinfunction "MIC1P_52") (pintype "bidirectional"))
    )
    (net (code "26") (name "HP_L") (class "Default")
      (node (ref "J3") (pin "12") (pinfunction "12_12") (pintype "bidirectional"))
      (node (ref "U1") (pin "53") (pinfunction "SPK1P_53") (pintype "bidirectional"))
    )
    (net (code "27") (name "HP_R") (class "Default")
      (node (ref "J3") (pin "11") (pinfunction "11_11") (pintype "bidirectional"))
      (node (ref "U1") (pin "13") (pinfunction "SPK1N_13") (pintype "bidirectional"))
    )
    (net (code "28") (name "MIC_N") (class "Default")
      (node (ref "J3") (pin "17") (pinfunction "17_17") (pintype "bidirectional"))
      (node (ref "U1") (pin "10") (pinfunction "MIC2N_10") (pintype "bidirectional"))
    )
    (net (code "29") (name "MIC_P") (class "Default")
      (node (ref "J3") (pin "18") (pinfunction "18_18") (pintype "bidirectional"))
      (node (ref "U1") (pin "9") (pinfunction "MIC2P_9") (pintype "bidirectional"))
    )
    (net (code "30") (name "Net-(BT-ANT)") (class "Default")
      (node (ref "BT") (pin "1") (pinfunction "ANT_1") (pintype "bidirectional"))
      (node (ref "C29") (pin "2") (pinfunction "2_2") (pintype "passive"))
      (node (ref "R18") (pin "2") (pinfunction "2_2") (pintype "passive"))
    )
    (net (code "31") (name "Net-(D1-Pad-)") (class "Default")
      (node (ref "D1") (pin "-") (pinfunction "-_-") (pintype "passive"))
      (node (ref "R37") (pin "1") (pinfunction "1_1") (pintype "passive"))
    )
    (net (code "32") (name "Net-(D3-Pad+)") (class "Default")
      (node (ref "D3") (pin "+") (pinfunction "+_+") (pintype "passive"))
      (node (ref "R7") (pin "1") (pinfunction "1_1") (pintype "passive"))
    )
    (net (code "33") (name "Net-(GSM-ANT)") (class "Default")
      (node (ref "C22") (pin "1") (pinfunction "1_1") (pintype "passive"))
      (node (ref "GSM") (pin "1") (pinfunction "ANT_1") (pintype "bidirectional"))
      (node (ref "R22") (pin "2") (pinfunction "2_2") (pintype "passive"))
    )
    (net (code "34") (name "Net-(J2-DM)") (class "Default")
      (node (ref "J2") (pin "2") (pinfunction "DM_2") (pintype "bidirectional"))
      (node (ref "R41") (pin "1") (pinfunction "1_1") (pintype "passive"))
    )
    (net (code "35") (name "Net-(J2-DP)") (class "Default")
      (node (ref "J2") (pin "3") (pinfunction "DP_3") (pintype "bidirectional"))
      (node (ref "R42") (pin "1") (pinfunction "1_1") (pintype "passive"))
    )
    (net (code "36") (name "Net-(K1-Pad2)") (class "Default")
      (node (ref "K1") (pin "2") (pinfunction "2_2") (pintype "bidirectional"))
      (node (ref "R12") (pin "1") (pinfunction "1_1") (pintype "passive"))
      (node (ref "R15") (pin "1") (pinfunction "1_1") (pintype "passive"))
    )
    (net (code "37") (name "Net-(L3-Pad1)") (class "Default")
      (node (ref "L3") (pin "1") (pinfunction "1_1") (pintype "passive"))
      (node (ref "U3") (pin "3") (pinfunction "SW_3") (pintype "bidirectional"))
      (node (ref "U3") (pin "4") (pinfunction "SW_4") (pintype "bidirectional"))
    )
    (net (code "38") (name "Net-(Q4-D)") (class "Default")
      (node (ref "D3") (pin "-") (pinfunction "-_-") (pintype "passive"))
      (node (ref "Q4") (pin "3") (pinfunction "D_3") (pintype "passive"))
    )
    (net (code "39") (name "Net-(Q4-G)") (class "Default")
      (node (ref "Q4") (pin "1") (pinfunction "G_1") (pintype "passive"))
      (node (ref "R14") (pin "2") (pinfunction "2_2") (pintype "passive"))
      (node (ref "R9") (pin "1") (pinfunction "1_1") (pintype "passive"))
    )
    (net (code "40") (name "Net-(Q5-D)") (class "Default")
      (node (ref "Q5") (pin "3") (pinfunction "D_3") (pintype "passive"))
      (node (ref "U1") (pin "48") (pinfunction "PWRKEY_48") (pintype "bidirectional"))
    )
    (net (code "41") (name "Net-(Q5-G)") (class "Default")
      (node (ref "Q5") (pin "1") (pinfunction "G_1") (pintype "passive"))
      (node (ref "R1") (pin "2") (pinfunction "2_2") (pintype "passive"))
      (node (ref "R13") (pin "1") (pinfunction "1_1") (pintype "passive"))
    )
    (net (code "42") (name "Net-(SIM-CLK)") (class "Default")
      (node (ref "C3") (pin "2") (pinfunction "2_2") (pintype "passive"))
      (node (ref "R2") (pin "2") (pinfunction "2_2") (pintype "passive"))
      (node (ref "SIM") (pin "3") (pinfunction "CLK_3") (pintype "bidirectional"))
    )
    (net (code "43") (name "Net-(SIM-I{slash}O)") (class "Default")
      (node (ref "C7") (pin "2") (pinfunction "2_2") (pintype "passive"))
      (node (ref "R4") (pin "1") (pinfunction "1_1") (pintype "passive"))
      (node (ref "SIM") (pin "7") (pinfunction "I/O_7") (pintype "bidirectional"))
    )
    (net (code "44") (name "Net-(SIM-RST)") (class "Default")
      (node (ref "C6") (pin "2") (pinfunction "2_2") (pintype "passive"))
      (node (ref "R3") (pin "2") (pinfunction "2_2") (pintype "passive"))
      (node (ref "SIM") (pin "2") (pinfunction "RST_2") (pintype "bidirectional"))
    )
    (net (code "45") (name "Net-(U1-ANT)") (class "Default")
      (node (ref "C28") (pin "1") (pinfunction "1_1") (pintype "passive"))
      (node (ref "R22") (pin "1") (pinfunction "1_1") (pintype "passive"))
      (node (ref "U1") (pin "40") (pinfunction "ANT_40") (pintype "bidirectional"))
    )
    (net (code "46") (name "Net-(U1-BT_ANT)") (class "Default")
      (node (ref "C30") (pin "2") (pinfunction "2_2") (pintype "passive"))
      (node (ref "R18") (pin "1") (pinfunction "1_1") (pintype "passive"))
      (node (ref "U1") (pin "36") (pinfunction "BT_ANT_36") (pintype "bidirectional"))
    )
    (net (code "47") (name "Net-(U1-FM_ANT_N)") (class "Default")
      (node (ref "TP2") (pin "T") (pinfunction "T_T") (pintype "bidirectional"))
      (node (ref "U1") (pin "57") (pinfunction "FM_ANT_N_57") (pintype "bidirectional"))
    )
    (net (code "48") (name "Net-(U1-FM_ANT_P)") (class "Default")
      (node (ref "TP3") (pin "T") (pinfunction "T_T") (pintype "bidirectional"))
      (node (ref "U1") (pin "17") (pinfunction "FM_ANT_P_17") (pintype "bidirectional"))
    )
    (net (code "49") (name "Net-(U1-NETLIGHT)") (class "Default")
      (node (ref "R14") (pin "1") (pinfunction "1_1") (pintype "passive"))
      (node (ref "U1") (pin "64") (pinfunction "NETLIGHT_64") (pintype "bidirectional"))
    )
    (net (code "50") (name "Net-(U1-RESET)") (class "Default")
      (node (ref "R17") (pin "1") (pinfunction "1_1") (pintype "passive"))
      (node (ref "U1") (pin "49") (pinfunction "RESET_49") (pintype "bidirectional"))
    )
    (net (code "51") (name "Net-(U1-STATUS)") (class "Default")
      (node (ref "TP1") (pin "T") (pinfunction "T_T") (pintype "bidirectional"))
      (node (ref "U1") (pin "4") (pinfunction "STATUS_4") (pintype "bidirectional"))
    )
    (net (code "52") (name "Net-(U1-VBUS)") (class "Default")
      (node (ref "TP4") (pin "T") (pinfunction "T_T") (pintype "bidirectional"))
      (node (ref "U1") (pin "7") (pinfunction "VBUS_7") (pintype "bidirectional"))
    )
    (net (code "53") (name "Net-(U1-VRTC)") (class "Default")
      (node (ref "C26") (pin "1") (pinfunction "1_1") (pintype "passive"))
      (node (ref "U1") (pin "56") (pinfunction "VRTC_56") (pintype "bidirectional"))
    )
    (net (code "54") (name "Net-(U3-ISET1)") (class "Default")
      (node (ref "R36") (pin "1") (pinfunction "1_1") (pintype "passive"))
      (node (ref "U3") (pin "11") (pinfunction "ISET1_11") (pintype "bidirectional"))
    )
    (net (code "55") (name "Net-(U3-ISET2)") (class "Default")
      (node (ref "R35") (pin "1") (pinfunction "1_1") (pintype "passive"))
      (node (ref "U3") (pin "12") (pinfunction "ISET2_12") (pintype "bidirectional"))
    )
    (net (code "56") (name "Net-(U3-NTC)") (class "Default")
      (node (ref "R38") (pin "1") (pinfunction "1_1") (pintype "passive"))
      (node (ref "R39") (pin "1") (pinfunction "1_1") (pintype "passive"))
      (node (ref "U3") (pin "7") (pinfunction "NTC_7") (pintype "bidirectional"))
    )
    (net (code "57") (name "Net-(U3-STAT)") (class "Default")
      (node (ref "R37") (pin "2") (pinfunction "2_2") (pintype "passive"))
      (node (ref "U3") (pin "9") (pinfunction "STAT_9") (pintype "bidirectional"))
    )
    (net (code "58") (name "Net-(U4-XTAL1)") (class "Default")
      (node (ref "U4") (pin "17") (pinfunction "XTAL1_17") (pintype "bidirectional"))
      (node (ref "X1") (pin "1") (pinfunction "1_1") (pintype "passive"))
    )
    (net (code "59") (name "Net-(U4-XTAL2)") (class "Default")
      (node (ref "U4") (pin "16") (pinfunction "XTAL2_16") (pintype "bidirectional"))
      (node (ref "X1") (pin "3") (pinfunction "3_3") (pintype "passive"))
    )
    (net (code "60") (name "Net-(U6-FB)") (class "Default")
      (node (ref "R11") (pin "1") (pinfunction "1_1") (pintype "passive"))
      (node (ref "R29") (pin "2") (pinfunction "2_2") (pintype "passive"))
      (node (ref "U6") (pin "4") (pinfunction "FB_4") (pintype "bidirectional"))
    )
    (net (code "61") (name "Net-(U6-SW)") (class "Default")
      (node (ref "L4") (pin "1") (pinfunction "1_1") (pintype "passive"))
      (node (ref "U6") (pin "2") (pinfunction "SW_2") (pintype "bidirectional"))
    )
    (net (code "62") (name "PB1{slash}D15{slash}SCK") (class "Default")
      (node (ref "J3") (pin "4") (pinfunction "4_4") (pintype "bidirectional"))
      (node (ref "J6") (pin "2") (pinfunction "2_2") (pintype "bidirectional"))
      (node (ref "U4") (pin "9") (pinfunction "PB1(PCINT1/SCLK)_9") (pintype "bidirectional"))
    )
    (net (code "63") (name "PB2{slash}D16{slash}MOSI") (class "Default")
      (node (ref "J3") (pin "8") (pinfunction "8_8") (pintype "bidirectional"))
      (node (ref "J6") (pin "5") (pinfunction "5_5") (pintype "bidirectional"))
      (node (ref "U4") (pin "10") (pinfunction "PB2(PDI/PCINT2/MOSI)_10") (pintype "bidirectional"))
    )
    (net (code "64") (name "PB3{slash}D14{slash}MISO") (class "Default")
      (node (ref "J3") (pin "7") (pinfunction "7_7") (pintype "bidirectional"))
      (node (ref "J6") (pin "1") (pinfunction "1_1") (pintype "bidirectional"))
      (node (ref "U4") (pin "11") (pinfunction "PB3(PD0/PCINT3/MISO)_11") (pintype "bidirectional"))
    )
    (net (code "65") (name "PF0{slash}A5") (class "Default")
      (node (ref "J3") (pin "23") (pinfunction "23_23") (pintype "bidirectional"))
      (node (ref "U4") (pin "41") (pinfunction "PF0(ADC0)_41") (pintype "bidirectional"))
    )
    (net (code "66") (name "PF1{slash}A4") (class "Default")
      (node (ref "J3") (pin "19") (pinfunction "19_19") (pintype "bidirectional"))
      (node (ref "U4") (pin "40") (pinfunction "PF1(ADC1)_40") (pintype "bidirectional"))
    )
    (net (code "67") (name "PF4{slash}A3") (class "Default")
      (node (ref "J3") (pin "20") (pinfunction "20_20") (pintype "bidirectional"))
      (node (ref "U4") (pin "39") (pinfunction "PF4(ADC4/TCK)_39") (pintype "bidirectional"))
    )
    (net (code "68") (name "PF5{slash}A2") (class "Default")
      (node (ref "J3") (pin "3") (pinfunction "3_3") (pintype "bidirectional"))
      (node (ref "R15") (pin "2") (pinfunction "2_2") (pintype "passive"))
      (node (ref "R16") (pin "2") (pinfunction "2_2") (pintype "passive"))
      (node (ref "U4") (pin "38") (pinfunction "PF5(ADC5/TMS)_38") (pintype "bidirectional"))
    )
    (net (code "69") (name "PF6{slash}A1") (class "Default")
      (node (ref "J3") (pin "22") (pinfunction "22_22") (pintype "bidirectional"))
      (node (ref "U4") (pin "37") (pinfunction "PF6(ADC6/TDO)_37") (pintype "bidirectional"))
    )
    (net (code "70") (name "PF7{slash}A0") (class "Default")
      (node (ref "J3") (pin "13") (pinfunction "13_13") (pintype "bidirectional"))
      (node (ref "U4") (pin "36") (pinfunction "PF7(ADC7/TDI)_36") (pintype "bidirectional"))
    )
    (net (code "71") (name "SIM_CLK") (class "Default")
      (node (ref "R2") (pin "1") (pinfunction "1_1") (pintype "passive"))
      (node (ref "U1") (pin "55") (pinfunction "SIM_CLK_55") (pintype "bidirectional"))
    )
    (net (code "72") (name "SIM_DATA") (class "Default")
      (node (ref "R4") (pin "2") (pinfunction "2_2") (pintype "passive"))
      (node (ref "U1") (pin "14") (pinfunction "SIM_DATA_14") (pintype "bidirectional"))
    )
    (net (code "73") (name "SIM_RST") (class "Default")
      (node (ref "R3") (pin "1") (pinfunction "1_1") (pintype "passive"))
      (node (ref "U1") (pin "15") (pinfunction "SIM_RST_15") (pintype "bidirectional"))
    )
    (net (code "74") (name "SIM_RXD") (class "Default")
      (node (ref "Q8") (pin "3") (pinfunction "D_3") (pintype "passive"))
      (node (ref "R8") (pin "2") (pinfunction "2_2") (pintype "passive"))
      (node (ref "U1") (pin "31") (pinfunction "UART1_RXD_31") (pintype "bidirectional"))
    )
    (net (code "75") (name "SIM_TXD") (class "Default")
      (node (ref "Q7") (pin "3") (pinfunction "D_3") (pintype "passive"))
      (node (ref "R6") (pin "2") (pinfunction "2_2") (pintype "passive"))
      (node (ref "U1") (pin "32") (pinfunction "UART1_TXD_32") (pintype "bidirectional"))
    )
    (net (code "76") (name "SPK_N") (class "Default")
      (node (ref "J3") (pin "9") (pinfunction "9_9") (pintype "bidirectional"))
      (node (ref "U1") (pin "11") (pinfunction "SPK2N_11") (pintype "bidirectional"))
    )
    (net (code "77") (name "SPK_P") (class "Default")
      (node (ref "J3") (pin "10") (pinfunction "10_10") (pintype "bidirectional"))
      (node (ref "U1") (pin "51") (pinfunction "SPK2P_51") (pintype "bidirectional"))
    )
    (net (code "78") (name "VCC_SIM") (class "Default")
      (node (ref "C1") (pin "2") (pinfunction "2_2") (pintype "passive"))
      (node (ref "C15") (pin "2") (pinfunction "2_2") (pintype "passive"))
      (node (ref "C19") (pin "2") (pinfunction "2_2") (pintype "passive"))
      (node (ref "C5") (pin "2") (pinfunction "2_2") (pintype "passive"))
      (node (ref "J1") (pin "10") (pinfunction "10_10") (pintype "bidirectional"))
      (node (ref "J1") (pin "2") (pinfunction "2_2") (pintype "bidirectional"))
      (node (ref "J10") (pin "3") (pinfunction "3_3") (pintype "bidirectional"))
      (node (ref "J3") (pin "27") (pinfunction "27_27") (pintype "bidirectional"))
      (node (ref "J3") (pin "28") (pinfunction "28_28") (pintype "bidirectional"))
      (node (ref "L4") (pin "2") (pinfunction "2_2") (pintype "passive"))
      (node (ref "R11") (pin "2") (pinfunction "2_2") (pintype "passive"))
      (node (ref "R17") (pin "2") (pinfunction "2_2") (pintype "passive"))
      (node (ref "R6") (pin "1") (pinfunction "1_1") (pintype "passive"))
      (node (ref "R8") (pin "1") (pinfunction "1_1") (pintype "passive"))
      (node (ref "U1") (pin "1") (pinfunction "VBAT_1") (pintype "bidirectional"))
      (node (ref "U1") (pin "42") (pinfunction "VBAT_42") (pintype "bidirectional"))
      (node (ref "U2") (pin "3") (pinfunction "VIN_3") (pintype "bidirectional"))
    )
    (net (code "79") (name "VSIM") (class "Default")
      (node (ref "C14") (pin "1") (pinfunction "1_1") (pintype "passive"))
      (node (ref "C2") (pin "1") (pinfunction "1_1") (pintype "passive"))
      (node (ref "SIM") (pin "1") (pinfunction "VCC_1") (pintype "bidirectional"))
      (node (ref "SIM") (pin "6") (pinfunction "VPP_6") (pintype "bidirectional"))
      (node (ref "U1") (pin "16") (pinfunction "VSIM_16") (pintype "bidirectional"))
    )
    (net (code "80") (name "VSYS") (class "Default")
      (node (ref "C13") (pin "1") (pinfunction "1_1") (pintype "passive"))
      (node (ref "C21") (pin "2") (pinfunction "2_2") (pintype "passive"))
      (node (ref "C27") (pin "2") (pinfunction "2_2") (pintype "passive"))
      (node (ref "D1") (pin "+") (pinfunction "+_+") (pintype "passive"))
      (node (ref "L3") (pin "2") (pinfunction "2_2") (pintype "passive"))
      (node (ref "TP6") (pin "T") (pinfunction "T_T") (pintype "bidirectional"))
      (node (ref "U3") (pin "1") (pinfunction "SYS_1") (pintype "bidirectional"))
      (node (ref "U3") (pin "15") (pinfunction "SYS_15") (pintype "bidirectional"))
      (node (ref "U6") (pin "5") (pinfunction "EN_5") (pintype "bidirectional"))
      (node (ref "U6") (pin "7") (pinfunction "AVIN_7") (pintype "bidirectional"))
      (node (ref "U6") (pin "8") (pinfunction "PVIN_8") (pintype "bidirectional"))
    )
    (net (code "81") (name "VUSB") (class "Default")
      (node (ref "C10") (pin "1") (pinfunction "1_1") (pintype "passive"))
      (node (ref "C23") (pin "1") (pinfunction "1_1") (pintype "passive"))
      (node (ref "C9") (pin "1") (pinfunction "1_1") (pintype "passive"))
      (node (ref "J2") (pin "1") (pinfunction "VCC_1") (pintype "bidirectional"))
      (node (ref "R38") (pin "2") (pinfunction "2_2") (pintype "passive"))
      (node (ref "R40") (pin "1") (pinfunction "1_1") (pintype "passive"))
      (node (ref "TP5") (pin "T") (pinfunction "T_T") (pintype "bidirectional"))
      (node (ref "U3") (pin "2") (pinfunction "IN_2") (pintype "bidirectional"))
      (node (ref "U4") (pin "2") (pinfunction "UVCC_2") (pintype "bidirectional"))
      (node (ref "U4") (pin "7") (pinfunction "VBUS_7") (pintype "bidirectional"))
    )
    (net (code "82") (name "unconnected-(J2-ID-Pad4)") (class "Default")
      (node (ref "J2") (pin "4") (pinfunction "ID_4") (pintype "bidirectional"))
    )
    (net (code "83") (name "unconnected-(TP8-PadT)") (class "Default")
      (node (ref "TP8") (pin "T") (pinfunction "T_T") (pintype "bidirectional"))
    )
    (net (code "84") (name "unconnected-(TP9-PadT)") (class "Default")
      (node (ref "TP9") (pin "T") (pinfunction "T_T") (pintype "bidirectional"))
    )
    (net (code "85") (name "unconnected-(U1-ADC-Pad50)") (class "Default")
      (node (ref "U1") (pin "50") (pinfunction "ADC_50") (pintype "bidirectional"))
    )
    (net (code "86") (name "unconnected-(U1-BPI_BUS1-Pad5)") (class "Default")
      (node (ref "U1") (pin "5") (pinfunction "BPI_BUS1_5") (pintype "bidirectional"))
    )
    (net (code "87") (name "unconnected-(U1-COL0-Pad20)") (class "Default")
      (node (ref "U1") (pin "20") (pinfunction "COL0_20") (pintype "bidirectional"))
    )
    (net (code "88") (name "unconnected-(U1-COL1-Pad25)") (class "Default")
      (node (ref "U1") (pin "25") (pinfunction "COL1_25") (pintype "bidirectional"))
    )
    (net (code "89") (name "unconnected-(U1-COL2-Pad22)") (class "Default")
      (node (ref "U1") (pin "22") (pinfunction "COL2_22") (pintype "bidirectional"))
    )
    (net (code "90") (name "unconnected-(U1-COL3-Pad21)") (class "Default")
      (node (ref "U1") (pin "21") (pinfunction "COL3_21") (pintype "bidirectional"))
    )
    (net (code "91") (name "unconnected-(U1-COL4-Pad24)") (class "Default")
      (node (ref "U1") (pin "24") (pinfunction "COL4_24") (pintype "bidirectional"))
    )
    (net (code "92") (name "unconnected-(U1-GPIO1-Pad3)") (class "Default")
      (node (ref "U1") (pin "3") (pinfunction "GPIO1_3") (pintype "bidirectional"))
    )
    (net (code "93") (name "unconnected-(U1-GPIO2-Pad27)") (class "Default")
      (node (ref "U1") (pin "27") (pinfunction "GPIO2_27") (pintype "bidirectional"))
    )
    (net (code "94") (name "unconnected-(U1-GPIO3-Pad28)") (class "Default")
      (node (ref "U1") (pin "28") (pinfunction "GPIO3_28") (pintype "bidirectional"))
    )
    (net (code "95") (name "unconnected-(U1-ISINK0-Pad47)") (class "Default")
      (node (ref "U1") (pin "47") (pinfunction "ISINK0_47") (pintype "bidirectional"))
    )
    (net (code "96") (name "unconnected-(U1-ISINK1-Pad46)") (class "Default")
      (node (ref "U1") (pin "46") (pinfunction "ISINK1_46") (pintype "bidirectional"))
    )
    (net (code "97") (name "unconnected-(U1-PCMCLK-Pad29)") (class "Default")
      (node (ref "U1") (pin "29") (pinfunction "PCMCLK_29") (pintype "bidirectional"))
    )
    (net (code "98") (name "unconnected-(U1-PCMIN-Pad66)") (class "Default")
      (node (ref "U1") (pin "66") (pinfunction "PCMIN_66") (pintype "bidirectional"))
    )
    (net (code "99") (name "unconnected-(U1-PCMOUT-Pad30)") (class "Default")
      (node (ref "U1") (pin "30") (pinfunction "PCMOUT_30") (pintype "bidirectional"))
    )
    (net (code "100") (name "unconnected-(U1-PCMSYNC-Pad65)") (class "Default")
      (node (ref "U1") (pin "65") (pinfunction "PCMSYNC_65") (pintype "bidirectional"))
    )
    (net (code "101") (name "unconnected-(U1-PWM-Pad26)") (class "Default")
      (node (ref "U1") (pin "26") (pinfunction "PWM_26") (pintype "bidirectional"))
    )
    (net (code "102") (name "unconnected-(U1-ROW0-Pad62)") (class "Default")
      (node (ref "U1") (pin "62") (pinfunction "ROW0_62") (pintype "bidirectional"))
    )
    (net (code "103") (name "unconnected-(U1-ROW1-Pad60)") (class "Default")
      (node (ref "U1") (pin "60") (pinfunction "ROW1_60") (pintype "bidirectional"))
    )
    (net (code "104") (name "unconnected-(U1-ROW2-Pad61)") (class "Default")
      (node (ref "U1") (pin "61") (pinfunction "ROW2_61") (pintype "bidirectional"))
    )
    (net (code "105") (name "unconnected-(U1-ROW3-Pad23)") (class "Default")
      (node (ref "U1") (pin "23") (pinfunction "ROW3_23") (pintype "bidirectional"))
    )
    (net (code "106") (name "unconnected-(U1-ROW4-Pad63)") (class "Default")
      (node (ref "U1") (pin "63") (pinfunction "ROW4_63") (pintype "bidirectional"))
    )
    (net (code "107") (name "unconnected-(U1-SCL-Pad74)") (class "Default")
      (node (ref "U1") (pin "74") (pinfunction "SCL_74") (pintype "bidirectional"))
    )
    (net (code "108") (name "unconnected-(U1-SDA-Pad75)") (class "Default")
      (node (ref "U1") (pin "75") (pinfunction "SDA_75") (pintype "bidirectional"))
    )
    (net (code "109") (name "unconnected-(U1-SIMPRE-Pad54)") (class "Default")
      (node (ref "U1") (pin "54") (pinfunction "SIMPRE_54") (pintype "bidirectional"))
    )
    (net (code "110") (name "unconnected-(U1-UART1_CTS-Pad34)") (class "Default")
      (node (ref "U1") (pin "34") (pinfunction "UART1_CTS_34") (pintype "bidirectional"))
    )
    (net (code "111") (name "unconnected-(U1-UART1_DCD-Pad70)") (class "Default")
      (node (ref "U1") (pin "70") (pinfunction "UART1_DCD_70") (pintype "bidirectional"))
    )
    (net (code "112") (name "unconnected-(U1-UART1_DTR-Pad69)") (class "Default")
      (node (ref "U1") (pin "69") (pinfunction "UART1_DTR_69") (pintype "bidirectional"))
    )
    (net (code "113") (name "unconnected-(U1-UART1_RI-Pad68)") (class "Default")
      (node (ref "U1") (pin "68") (pinfunction "UART1_RI_68") (pintype "bidirectional"))
    )
    (net (code "114") (name "unconnected-(U1-UART1_RTS-Pad33)") (class "Default")
      (node (ref "U1") (pin "33") (pinfunction "UART1_RTS_33") (pintype "bidirectional"))
    )
    (net (code "115") (name "unconnected-(U1-USB_DM-Pad19)") (class "Default")
      (node (ref "U1") (pin "19") (pinfunction "USB_DM_19") (pintype "bidirectional"))
    )
    (net (code "116") (name "unconnected-(U1-USB_DP-Pad59)") (class "Default")
      (node (ref "U1") (pin "59") (pinfunction "USB_DP_59") (pintype "bidirectional"))
    )
    (net (code "117") (name "unconnected-(U1-VEXT-Pad18)") (class "Default")
      (node (ref "U1") (pin "18") (pinfunction "VEXT_18") (pintype "bidirectional"))
    )
    (net (code "118") (name "unconnected-(U4-PB0(SS{slash}PCINT0)-Pad8)") (class "Default")
      (node (ref "U4") (pin "8") (pinfunction "PB0(SS/PCINT0)_8") (pintype "bidirectional"))
    )
    (net (code "119") (name "unconnected-(U4-PD5(XCLK1{slash}~{CTS})-Pad22)") (class "Default")
      (node (ref "U4") (pin "22") (pinfunction "PD5(XCLK1/~{CTS})_22") (pintype "bidirectional"))
    )
  )
)
